# FeatherTriac.net
KiCad netlist of a schematic drawn in EAGLE
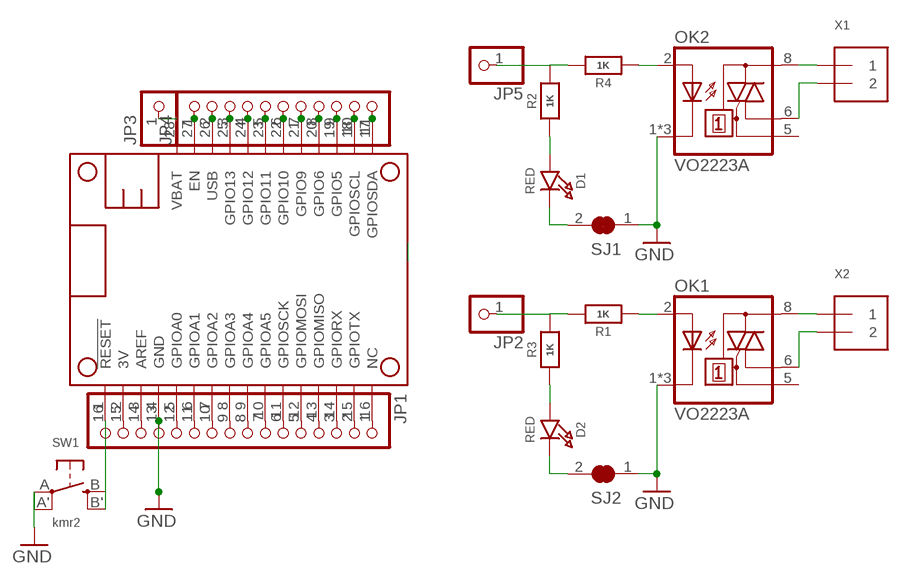
[diagram p0: schematic, sheet 1]

(export (version "E")
  (design (tool "Eeschema 10.0.6"))
  (components
    (comp (ref "D1")
      (value "RED")
      (footprint "eagle-import:CHIPLED_0805_NOOUTLINE")
      (libsource (lib "eagle-import") (part "LED0805_NOOUTLINE"))
    )
    (comp (ref "D2")
      (value "RED")
      (footprint "eagle-import:CHIPLED_0805_NOOUTLINE")
      (libsource (lib "eagle-import") (part "LED0805_NOOUTLINE"))
    )
    (comp (ref "JP1")
      (value "HEADER-1X16ROUND")
      (footprint "eagle-import:1X16_ROUND")
      (libsource (lib "eagle-import") (part "HEADER-1X16ROUND"))
    )
    (comp (ref "JP2")
      (value "HEADER-1X1ROUND")
      (footprint "eagle-import:1X01_ROUND")
      (libsource (lib "eagle-import") (part "HEADER-1X1ROUND"))
    )
    (comp (ref "JP3")
      (value "HEADER-1X1ROUND")
      (footprint "eagle-import:1X01_ROUND")
      (libsource (lib "eagle-import") (part "HEADER-1X1ROUND"))
    )
    (comp (ref "JP4")
      (value "HEADER-1X11")
      (footprint "eagle-import:1X11_ROUND")
      (libsource (lib "eagle-import") (part "HEADER-1X11"))
    )
    (comp (ref "JP5")
      (value "HEADER-1X1ROUND")
      (footprint "eagle-import:1X01_ROUND")
      (libsource (lib "eagle-import") (part "HEADER-1X1ROUND"))
    )
    (comp (ref "MS1")
      (value "MICROSHIELD")
      (footprint "eagle-import:MICROSHIELD")
      (libsource (lib "eagle-import") (part "MICROSHIELD"))
    )
    (comp (ref "OK1")
      (value "VO2223A")
      (footprint "eagle-import:DIL7")
      (libsource (lib "eagle-import") (part "VO2223A"))
    )
    (comp (ref "OK2")
      (value "VO2223A")
      (footprint "eagle-import:DIL7")
      (libsource (lib "eagle-import") (part "VO2223A"))
    )
    (comp (ref "R1")
      (value "1K")
      (footprint "eagle-import:0805-NO")
      (libsource (lib "eagle-import") (part "RESISTOR0805_NOOUTLINE"))
    )
    (comp (ref "R2")
      (value "1K")
      (footprint "eagle-import:0805-NO")
      (libsource (lib "eagle-import") (part "RESISTOR0805_NOOUTLINE"))
    )
    (comp (ref "R3")
      (value "1K")
      (footprint "eagle-import:0805-NO")
      (libsource (lib "eagle-import") (part "RESISTOR0805_NOOUTLINE"))
    )
    (comp (ref "R4")
      (value "1K")
      (footprint "eagle-import:0805-NO")
      (libsource (lib "eagle-import") (part "RESISTOR0805_NOOUTLINE"))
    )
    (comp (ref "SJ1")
      (value "SOLDERJUMPER_CLOSED")
      (footprint "eagle-import:SOLDERJUMPER_CLOSEDWIRE")
      (libsource (lib "eagle-import") (part "SOLDERJUMPER_CLOSED"))
    )
    (comp (ref "SJ2")
      (value "SOLDERJUMPER_CLOSED")
      (footprint "eagle-import:SOLDERJUMPER_CLOSEDWIRE")
      (libsource (lib "eagle-import") (part "SOLDERJUMPER_CLOSED"))
    )
    (comp (ref "SW1")
      (value "kmr2")
      (footprint "eagle-import:BTN_KMR2_4.6X2.8")
      (libsource (lib "eagle-import") (part "SWITCH_TACT_SMT4.6X2.8"))
    )
    (comp (ref "X1")
      (value "TERMBLOCK_1X2")
      (footprint "eagle-import:TERMBLOCK_1X2-3.5MM")
      (libsource (lib "eagle-import") (part "TERMBLOCK_1X2"))
    )
    (comp (ref "X2")
      (value "TERMBLOCK_1X2")
      (footprint "eagle-import:TERMBLOCK_1X2-3.5MM")
      (libsource (lib "eagle-import") (part "TERMBLOCK_1X2"))
    )
  )
  (nets
    (net (code "1") (name "/N$1") (class "Default")
      (node (ref "D2") (pin "A") (pinfunction "A_A") (pintype "passive"))
      (node (ref "R3") (pin "1") (pinfunction "1_1") (pintype "passive"))
    )
    (net (code "2") (name "GND") (class "Default")
      (node (ref "JP1") (pin "13") (pinfunction "13_13") (pintype "passive"))
      (node (ref "MS1") (pin "4") (pinfunction "GND_4") (pintype "power_in"))
      (node (ref "OK1") (pin "1") (pinfunction "C_1") (pintype "passive"))
      (node (ref "OK1") (pin "3") (pinfunction "C_3") (pintype "passive"))
      (node (ref "OK1") (pin "4") (pinfunction "C_4") (pintype "passive"))
      (node (ref "OK2") (pin "1") (pinfunction "C_1") (pintype "passive"))
      (node (ref "OK2") (pin "3") (pinfunction "C_3") (pintype "passive"))
      (node (ref "OK2") (pin "4") (pinfunction "C_4") (pintype "passive"))
      (node (ref "SJ1") (pin "1") (pinfunction "1_1") (pintype "passive"))
      (node (ref "SJ2") (pin "1") (pinfunction "1_1") (pintype "passive"))
      (node (ref "SW1") (pin "A") (pinfunction "P_A") (pintype "passive"))
      (node (ref "SW1") (pin "A'") (pinfunction "P1_A'") (pintype "passive"))
    )
    (net (code "3") (name "Net-(D1-PadA)") (class "Default")
      (node (ref "D1") (pin "A") (pinfunction "A_A") (pintype "passive"))
      (node (ref "R2") (pin "1") (pinfunction "1_1") (pintype "passive"))
    )
    (net (code "4") (name "Net-(D1-PadC)") (class "Default")
      (node (ref "D1") (pin "C") (pinfunction "C_C") (pintype "passive"))
      (node (ref "SJ1") (pin "2") (pinfunction "2_2") (pintype "passive"))
    )
    (net (code "5") (name "Net-(D2-PadC)") (class "Default")
      (node (ref "D2") (pin "C") (pinfunction "C_C") (pintype "passive"))
      (node (ref "SJ2") (pin "2") (pinfunction "2_2") (pintype "passive"))
    )
    (net (code "6") (name "Net-(JP2-Pad1)") (class "Default")
      (node (ref "JP2") (pin "1") (pinfunction "1_1") (pintype "passive"))
      (node (ref "R1") (pin "2") (pinfunction "2_2") (pintype "passive"))
      (node (ref "R3") (pin "2") (pinfunction "2_2") (pintype "passive"))
    )
    (net (code "7") (name "Net-(JP5-Pad1)") (class "Default")
      (node (ref "JP5") (pin "1") (pinfunction "1_1") (pintype "passive"))
      (node (ref "R2") (pin "2") (pinfunction "2_2") (pintype "passive"))
      (node (ref "R4") (pin "2") (pinfunction "2_2") (pintype "passive"))
    )
    (net (code "8") (name "Net-(MS1-3V)") (class "Default")
      (node (ref "JP1") (pin "15") (pinfunction "15_15") (pintype "passive"))
      (node (ref "MS1") (pin "2") (pinfunction "3V_2") (pintype "power_in"))
    )
    (net (code "9") (name "Net-(MS1-AREF)") (class "Default")
      (node (ref "JP1") (pin "14") (pinfunction "14_14") (pintype "passive"))
      (node (ref "MS1") (pin "3") (pinfunction "AREF_3") (pintype "passive"))
    )
    (net (code "10") (name "Net-(MS1-EN)") (class "Default")
      (node (ref "JP4") (pin "1") (pinfunction "1_1") (pintype "passive"))
      (node (ref "MS1") (pin "27") (pinfunction "EN_27") (pintype "passive"))
    )
    (net (code "11") (name "Net-(MS1-GPIO5)") (class "Default")
      (node (ref "JP4") (pin "9") (pinfunction "9_9") (pintype "passive"))
      (node (ref "MS1") (pin "19") (pinfunction "GPIO5_19") (pintype "bidirectional"))
    )
    (net (code "12") (name "Net-(MS1-GPIO6)") (class "Default")
      (node (ref "JP4") (pin "8") (pinfunction "8_8") (pintype "passive"))
      (node (ref "MS1") (pin "20") (pinfunction "GPIO6_20") (pintype "bidirectional"))
    )
    (net (code "13") (name "Net-(MS1-GPIO9)") (class "Default")
      (node (ref "JP4") (pin "7") (pinfunction "7_7") (pintype "passive"))
      (node (ref "MS1") (pin "21") (pinfunction "GPIO9_21") (pintype "bidirectional"))
    )
    (net (code "14") (name "Net-(MS1-GPIO10)") (class "Default")
      (node (ref "JP4") (pin "6") (pinfunction "6_6") (pintype "passive"))
      (node (ref "MS1") (pin "22") (pinfunction "GPIO10_22") (pintype "bidirectional"))
    )
    (net (code "15") (name "Net-(MS1-GPIO11)") (class "Default")
      (node (ref "JP4") (pin "5") (pinfunction "5_5") (pintype "passive"))
      (node (ref "MS1") (pin "23") (pinfunction "GPIO11_23") (pintype "bidirectional"))
    )
    (net (code "16") (name "Net-(MS1-GPIO12)") (class "Default")
      (node (ref "JP4") (pin "4") (pinfunction "4_4") (pintype "passive"))
      (node (ref "MS1") (pin "24") (pinfunction "GPIO12_24") (pintype "bidirectional"))
    )
    (net (code "17") (name "Net-(MS1-GPIO13)") (class "Default")
      (node (ref "JP4") (pin "3") (pinfunction "3_3") (pintype "passive"))
      (node (ref "MS1") (pin "25") (pinfunction "GPIO13_25") (pintype "bidirectional"))
    )
    (net (code "18") (name "Net-(MS1-GPIOA0)") (class "Default")
      (node (ref "JP1") (pin "12") (pinfunction "12_12") (pintype "passive"))
      (node (ref "MS1") (pin "5") (pinfunction "GPIOA0_5") (pintype "bidirectional"))
    )
    (net (code "19") (name "Net-(MS1-GPIOA1)") (class "Default")
      (node (ref "JP1") (pin "11") (pinfunction "11_11") (pintype "passive"))
      (node (ref "MS1") (pin "6") (pinfunction "GPIOA1_6") (pintype "bidirectional"))
    )
    (net (code "20") (name "Net-(MS1-GPIOA2)") (class "Default")
      (node (ref "JP1") (pin "10") (pinfunction "10_10") (pintype "passive"))
      (node (ref "MS1") (pin "7") (pinfunction "GPIOA2_7") (pintype "bidirectional"))
    )
    (net (code "21") (name "Net-(MS1-GPIOA3)") (class "Default")
      (node (ref "JP1") (pin "9") (pinfunction "9_9") (pintype "passive"))
      (node (ref "MS1") (pin "8") (pinfunction "GPIOA3_8") (pintype "bidirectional"))
    )
    (net (code "22") (name "Net-(MS1-GPIOA4)") (class "Default")
      (node (ref "JP1") (pin "8") (pinfunction "8_8") (pintype "passive"))
      (node (ref "MS1") (pin "9") (pinfunction "GPIOA4_9") (pintype "bidirectional"))
    )
    (net (code "23") (name "Net-(MS1-GPIOA5)") (class "Default")
      (node (ref "JP1") (pin "7") (pinfunction "7_7") (pintype "passive"))
      (node (ref "MS1") (pin "10") (pinfunction "GPIOA5_10") (pintype "bidirectional"))
    )
    (net (code "24") (name "Net-(MS1-GPIOMISO)") (class "Default")
      (node (ref "JP1") (pin "4") (pinfunction "4_4") (pintype "passive"))
      (node (ref "MS1") (pin "13") (pinfunction "GPIOMISO_13") (pintype "bidirectional"))
    )
    (net (code "25") (name "Net-(MS1-GPIOMOSI)") (class "Default")
      (node (ref "JP1") (pin "5") (pinfunction "5_5") (pintype "passive"))
      (node (ref "MS1") (pin "12") (pinfunction "GPIOMOSI_12") (pintype "bidirectional"))
    )
    (net (code "26") (name "Net-(MS1-GPIORX)") (class "Default")
      (node (ref "JP1") (pin "3") (pinfunction "3_3") (pintype "passive"))
      (node (ref "MS1") (pin "14") (pinfunction "GPIORX_14") (pintype "bidirectional"))
    )
    (net (code "27") (name "Net-(MS1-GPIOSCK)") (class "Default")
      (node (ref "JP1") (pin "6") (pinfunction "6_6") (pintype "passive"))
      (node (ref "MS1") (pin "11") (pinfunction "GPIOSCK_11") (pintype "bidirectional"))
    )
    (net (code "28") (name "Net-(MS1-GPIOSCL)") (class "Default")
      (node (ref "JP4") (pin "10") (pinfunction "10_10") (pintype "passive"))
      (node (ref "MS1") (pin "18") (pinfunction "GPIOSCL_18") (pintype "bidirectional"))
    )
    (net (code "29") (name "Net-(MS1-GPIOSDA)") (class "Default")
      (node (ref "JP4") (pin "11") (pinfunction "11_11") (pintype "passive"))
      (node (ref "MS1") (pin "17") (pinfunction "GPIOSDA_17") (pintype "bidirectional"))
    )
    (net (code "30") (name "Net-(MS1-GPIOTX)") (class "Default")
      (node (ref "JP1") (pin "2") (pinfunction "2_2") (pintype "passive"))
      (node (ref "MS1") (pin "15") (pinfunction "GPIOTX_15") (pintype "bidirectional"))
    )
    (net (code "31") (name "Net-(MS1-NC)") (class "Default")
      (node (ref "JP1") (pin "1") (pinfunction "1_1") (pintype "passive"))
      (node (ref "MS1") (pin "16") (pinfunction "NC_16") (pintype "passive"))
    )
    (net (code "32") (name "Net-(MS1-USB)") (class "Default")
      (node (ref "JP4") (pin "2") (pinfunction "2_2") (pintype "passive"))
      (node (ref "MS1") (pin "26") (pinfunction "USB_26") (pintype "power_in"))
    )
    (net (code "33") (name "Net-(MS1-VBAT)") (class "Default")
      (node (ref "JP3") (pin "1") (pinfunction "1_1") (pintype "passive"))
      (node (ref "MS1") (pin "28") (pinfunction "VBAT_28") (pintype "power_in"))
    )
    (net (code "34") (name "Net-(MS1-~{RESET})") (class "Default")
      (node (ref "JP1") (pin "16") (pinfunction "16_16") (pintype "passive"))
      (node (ref "MS1") (pin "1") (pinfunction "~{RESET}_1") (pintype "input"))
      (node (ref "SW1") (pin "B") (pinfunction "S_B") (pintype "passive"))
      (node (ref "SW1") (pin "B'") (pinfunction "S1_B'") (pintype "passive"))
    )
    (net (code "35") (name "Net-(OK1-A)") (class "Default")
      (node (ref "OK1") (pin "2") (pinfunction "A_2") (pintype "passive"))
      (node (ref "R1") (pin "1") (pinfunction "1_1") (pintype "passive"))
    )
    (net (code "36") (name "Net-(OK1-T1)") (class "Default")
      (node (ref "OK1") (pin "6") (pinfunction "T1_6") (pintype "passive"))
      (node (ref "X2") (pin "2") (pinfunction "2_2") (pintype "passive"))
    )
    (net (code "37") (name "Net-(OK1-T2)") (class "Default")
      (node (ref "OK1") (pin "8") (pinfunction "T2_8") (pintype "passive"))
      (node (ref "X2") (pin "1") (pinfunction "1_1") (pintype "passive"))
    )
    (net (code "38") (name "Net-(OK2-A)") (class "Default")
      (node (ref "OK2") (pin "2") (pinfunction "A_2") (pintype "passive"))
      (node (ref "R4") (pin "1") (pinfunction "1_1") (pintype "passive"))
    )
    (net (code "39") (name "Net-(OK2-T1)") (class "Default")
      (node (ref "OK2") (pin "6") (pinfunction "T1_6") (pintype "passive"))
      (node (ref "X1") (pin "2") (pinfunction "2_2") (pintype "passive"))
    )
    (net (code "40") (name "Net-(OK2-T2)") (class "Default")
      (node (ref "OK2") (pin "8") (pinfunction "T2_8") (pintype "passive"))
      (node (ref "X1") (pin "1") (pinfunction "1_1") (pintype "passive"))
    )
    (net (code "41") (name "unconnected-(OK1-G-Pad5)") (class "Default")
      (node (ref "OK1") (pin "5") (pinfunction "G_5") (pintype "passive"))
    )
    (net (code "42") (name "unconnected-(OK2-G-Pad5)") (class "Default")
      (node (ref "OK2") (pin "5") (pinfunction "G_5") (pintype "passive"))
    )
  )
)
